# 1_P1.net
KiCad netlist of a schematic drawn in Altium Designer
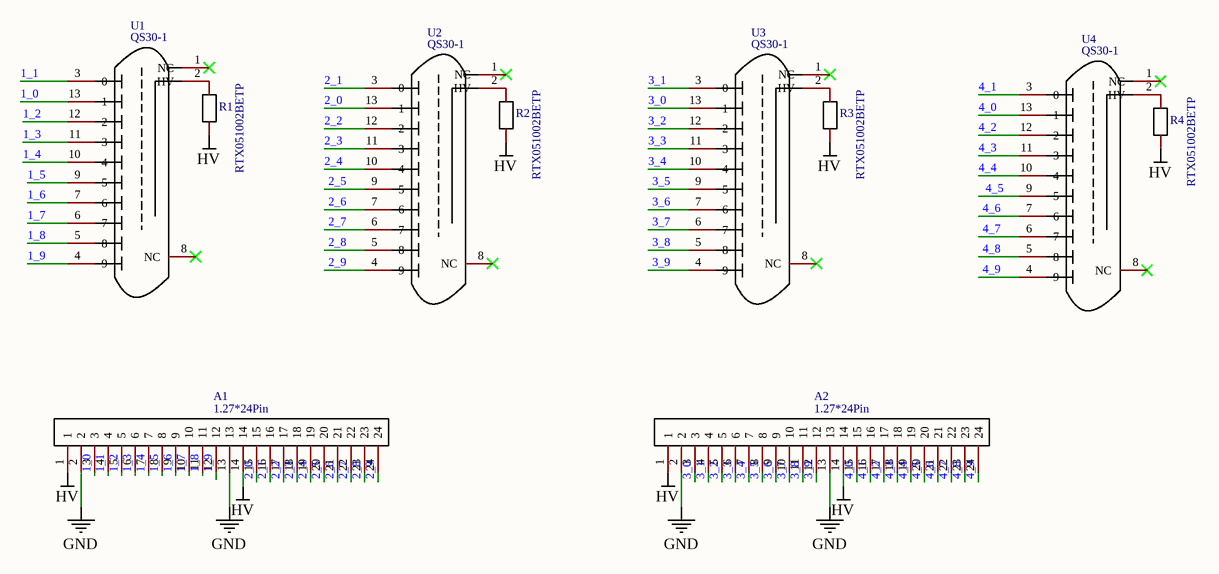
[diagram p0: 1_P1.schdoc]

(export (version "E")
  (design (tool "Eeschema 10.0.6"))
  (components
    (comp (ref "A1")
      (value "1.27*24Pin")
      (fields (field (name "NAME") "1.27*24Pin"))
      (libsource (lib "altium-import") (part "root_1_1.27*24Pin_"))
    )
    (comp (ref "A2")
      (value "1.27*24Pin")
      (fields (field (name "NAME") "1.27*24Pin"))
      (libsource (lib "altium-import") (part "root_1_1.27*24Pin_"))
    )
    (comp (ref "R1")
      (value "RTX051002BETP")
      (fields (field (name "NAME") "RTX051002BETP") (field (name "MANUFACTURER") "RALEC(旺诠)"))
      (libsource (lib "altium-import") (part "root_1_RTX051002BETP_"))
    )
    (comp (ref "R2")
      (value "RTX051002BETP")
      (fields (field (name "NAME") "RTX051002BETP") (field (name "MANUFACTURER") "RALEC(旺诠)"))
      (libsource (lib "altium-import") (part "root_1_RTX051002BETP_"))
    )
    (comp (ref "R3")
      (value "RTX051002BETP")
      (fields (field (name "NAME") "RTX051002BETP") (field (name "MANUFACTURER") "RALEC(旺诠)"))
      (libsource (lib "altium-import") (part "root_1_RTX051002BETP_"))
    )
    (comp (ref "R4")
      (value "RTX051002BETP")
      (fields (field (name "NAME") "RTX051002BETP") (field (name "MANUFACTURER") "RALEC(旺诠)"))
      (libsource (lib "altium-import") (part "root_1_RTX051002BETP_"))
    )
    (comp (ref "U1")
      (value "QS30-1")
      (fields (field (name "NAME") "QS30-1"))
      (libsource (lib "altium-import") (part "root_3_QS30-1_"))
    )
    (comp (ref "U2")
      (value "QS30-1")
      (fields (field (name "NAME") "QS30-1"))
      (libsource (lib "altium-import") (part "root_3_QS30-1_"))
    )
    (comp (ref "U3")
      (value "QS30-1")
      (fields (field (name "NAME") "QS30-1"))
      (libsource (lib "altium-import") (part "root_3_QS30-1_"))
    )
    (comp (ref "U4")
      (value "QS30-1")
      (fields (field (name "NAME") "QS30-1"))
      (libsource (lib "altium-import") (part "root_3_QS30-1_"))
    )
  )
  (nets
    (net (code "1") (name "/1_0") (class "Default")
      (node (ref "A1") (pin "3") (pinfunction "3_3") (pintype "passive"))
      (node (ref "U1") (pin "13") (pinfunction "1_13") (pintype "passive"))
    )
    (net (code "2") (name "/1_1") (class "Default")
      (node (ref "A1") (pin "4") (pinfunction "4_4") (pintype "passive"))
      (node (ref "U1") (pin "3") (pinfunction "0_3") (pintype "passive"))
    )
    (net (code "3") (name "/1_2") (class "Default")
      (node (ref "A1") (pin "5") (pinfunction "5_5") (pintype "passive"))
      (node (ref "U1") (pin "12") (pinfunction "2_12") (pintype "passive"))
    )
    (net (code "4") (name "/1_3") (class "Default")
      (node (ref "A1") (pin "6") (pinfunction "6_6") (pintype "passive"))
      (node (ref "U1") (pin "11") (pinfunction "3_11") (pintype "passive"))
    )
    (net (code "5") (name "/1_4") (class "Default")
      (node (ref "A1") (pin "7") (pinfunction "7_7") (pintype "passive"))
      (node (ref "U1") (pin "10") (pinfunction "4_10") (pintype "passive"))
    )
    (net (code "6") (name "/1_5") (class "Default")
      (node (ref "A1") (pin "8") (pinfunction "8_8") (pintype "passive"))
      (node (ref "U1") (pin "9") (pinfunction "5_9") (pintype "passive"))
    )
    (net (code "7") (name "/1_6") (class "Default")
      (node (ref "A1") (pin "9") (pinfunction "9_9") (pintype "passive"))
      (node (ref "U1") (pin "7") (pinfunction "6_7") (pintype "passive"))
    )
    (net (code "8") (name "/1_7") (class "Default")
      (node (ref "A1") (pin "10") (pinfunction "10_10") (pintype "passive"))
      (node (ref "U1") (pin "6") (pinfunction "7_6") (pintype "passive"))
    )
    (net (code "9") (name "/1_8") (class "Default")
      (node (ref "A1") (pin "11") (pinfunction "11_11") (pintype "passive"))
      (node (ref "U1") (pin "5") (pinfunction "8_5") (pintype "passive"))
    )
    (net (code "10") (name "/1_9") (class "Default")
      (node (ref "A1") (pin "12") (pinfunction "12_12") (pintype "passive"))
      (node (ref "U1") (pin "4") (pinfunction "9_4") (pintype "passive"))
    )
    (net (code "11") (name "/2_0") (class "Default")
      (node (ref "A1") (pin "15") (pinfunction "15_15") (pintype "passive"))
      (node (ref "U2") (pin "13") (pinfunction "1_13") (pintype "passive"))
    )
    (net (code "12") (name "/2_1") (class "Default")
      (node (ref "A1") (pin "16") (pinfunction "16_16") (pintype "passive"))
      (node (ref "U2") (pin "3") (pinfunction "0_3") (pintype "passive"))
    )
    (net (code "13") (name "/2_2") (class "Default")
      (node (ref "A1") (pin "17") (pinfunction "17_17") (pintype "passive"))
      (node (ref "U2") (pin "12") (pinfunction "2_12") (pintype "passive"))
    )
    (net (code "14") (name "/2_3") (class "Default")
      (node (ref "A1") (pin "18") (pinfunction "18_18") (pintype "passive"))
      (node (ref "U2") (pin "11") (pinfunction "3_11") (pintype "passive"))
    )
    (net (code "15") (name "/2_4") (class "Default")
      (node (ref "A1") (pin "19") (pinfunction "19_19") (pintype "passive"))
      (node (ref "U2") (pin "10") (pinfunction "4_10") (pintype "passive"))
    )
    (net (code "16") (name "/2_5") (class "Default")
      (node (ref "A1") (pin "20") (pinfunction "20_20") (pintype "passive"))
      (node (ref "U2") (pin "9") (pinfunction "5_9") (pintype "passive"))
    )
    (net (code "17") (name "/2_6") (class "Default")
      (node (ref "A1") (pin "21") (pinfunction "21_21") (pintype "passive"))
      (node (ref "U2") (pin "7") (pinfunction "6_7") (pintype "passive"))
    )
    (net (code "18") (name "/2_7") (class "Default")
      (node (ref "A1") (pin "22") (pinfunction "22_22") (pintype "passive"))
      (node (ref "U2") (pin "6") (pinfunction "7_6") (pintype "passive"))
    )
    (net (code "19") (name "/2_8") (class "Default")
      (node (ref "A1") (pin "23") (pinfunction "23_23") (pintype "passive"))
      (node (ref "U2") (pin "5") (pinfunction "8_5") (pintype "passive"))
    )
    (net (code "20") (name "/2_9") (class "Default")
      (node (ref "A1") (pin "24") (pinfunction "24_24") (pintype "passive"))
      (node (ref "U2") (pin "4") (pinfunction "9_4") (pintype "passive"))
    )
    (net (code "21") (name "/3_0") (class "Default")
      (node (ref "A2") (pin "3") (pinfunction "3_3") (pintype "passive"))
      (node (ref "U3") (pin "13") (pinfunction "1_13") (pintype "passive"))
    )
    (net (code "22") (name "/3_1") (class "Default")
      (node (ref "A2") (pin "4") (pinfunction "4_4") (pintype "passive"))
      (node (ref "U3") (pin "3") (pinfunction "0_3") (pintype "passive"))
    )
    (net (code "23") (name "/3_2") (class "Default")
      (node (ref "A2") (pin "5") (pinfunction "5_5") (pintype "passive"))
      (node (ref "U3") (pin "12") (pinfunction "2_12") (pintype "passive"))
    )
    (net (code "24") (name "/3_3") (class "Default")
      (node (ref "A2") (pin "6") (pinfunction "6_6") (pintype "passive"))
      (node (ref "U3") (pin "11") (pinfunction "3_11") (pintype "passive"))
    )
    (net (code "25") (name "/3_4") (class "Default")
      (node (ref "A2") (pin "7") (pinfunction "7_7") (pintype "passive"))
      (node (ref "U3") (pin "10") (pinfunction "4_10") (pintype "passive"))
    )
    (net (code "26") (name "/3_5") (class "Default")
      (node (ref "A2") (pin "8") (pinfunction "8_8") (pintype "passive"))
      (node (ref "U3") (pin "9") (pinfunction "5_9") (pintype "passive"))
    )
    (net (code "27") (name "/3_6") (class "Default")
      (node (ref "A2") (pin "9") (pinfunction "9_9") (pintype "passive"))
      (node (ref "U3") (pin "7") (pinfunction "6_7") (pintype "passive"))
    )
    (net (code "28") (name "/3_7") (class "Default")
      (node (ref "A2") (pin "10") (pinfunction "10_10") (pintype "passive"))
      (node (ref "U3") (pin "6") (pinfunction "7_6") (pintype "passive"))
    )
    (net (code "29") (name "/3_8") (class "Default")
      (node (ref "A2") (pin "11") (pinfunction "11_11") (pintype "passive"))
      (node (ref "U3") (pin "5") (pinfunction "8_5") (pintype "passive"))
    )
    (net (code "30") (name "/3_9") (class "Default")
      (node (ref "A2") (pin "12") (pinfunction "12_12") (pintype "passive"))
      (node (ref "U3") (pin "4") (pinfunction "9_4") (pintype "passive"))
    )
    (net (code "31") (name "/4_0") (class "Default")
      (node (ref "A2") (pin "15") (pinfunction "15_15") (pintype "passive"))
      (node (ref "U4") (pin "13") (pinfunction "1_13") (pintype "passive"))
    )
    (net (code "32") (name "/4_1") (class "Default")
      (node (ref "A2") (pin "16") (pinfunction "16_16") (pintype "passive"))
      (node (ref "U4") (pin "3") (pinfunction "0_3") (pintype "passive"))
    )
    (net (code "33") (name "/4_2") (class "Default")
      (node (ref "A2") (pin "17") (pinfunction "17_17") (pintype "passive"))
      (node (ref "U4") (pin "12") (pinfunction "2_12") (pintype "passive"))
    )
    (net (code "34") (name "/4_3") (class "Default")
      (node (ref "A2") (pin "18") (pinfunction "18_18") (pintype "passive"))
      (node (ref "U4") (pin "11") (pinfunction "3_11") (pintype "passive"))
    )
    (net (code "35") (name "/4_4") (class "Default")
      (node (ref "A2") (pin "19") (pinfunction "19_19") (pintype "passive"))
      (node (ref "U4") (pin "10") (pinfunction "4_10") (pintype "passive"))
    )
    (net (code "36") (name "/4_5") (class "Default")
      (node (ref "A2") (pin "20") (pinfunction "20_20") (pintype "passive"))
      (node (ref "U4") (pin "9") (pinfunction "5_9") (pintype "passive"))
    )
    (net (code "37") (name "/4_6") (class "Default")
      (node (ref "A2") (pin "21") (pinfunction "21_21") (pintype "passive"))
      (node (ref "U4") (pin "7") (pinfunction "6_7") (pintype "passive"))
    )
    (net (code "38") (name "/4_7") (class "Default")
      (node (ref "A2") (pin "22") (pinfunction "22_22") (pintype "passive"))
      (node (ref "U4") (pin "6") (pinfunction "7_6") (pintype "passive"))
    )
    (net (code "39") (name "/4_8") (class "Default")
      (node (ref "A2") (pin "23") (pinfunction "23_23") (pintype "passive"))
      (node (ref "U4") (pin "5") (pinfunction "8_5") (pintype "passive"))
    )
    (net (code "40") (name "/4_9") (class "Default")
      (node (ref "A2") (pin "24") (pinfunction "24_24") (pintype "passive"))
      (node (ref "U4") (pin "4") (pinfunction "9_4") (pintype "passive"))
    )
    (net (code "41") (name "GND") (class "Default")
      (node (ref "A1") (pin "13") (pinfunction "13_13") (pintype "passive"))
      (node (ref "A1") (pin "2") (pinfunction "2_2") (pintype "passive"))
      (node (ref "A2") (pin "13") (pinfunction "13_13") (pintype "passive"))
      (node (ref "A2") (pin "2") (pinfunction "2_2") (pintype "passive"))
    )
    (net (code "42") (name "HV") (class "Default")
      (node (ref "A1") (pin "1") (pinfunction "1_1") (pintype "passive"))
      (node (ref "A1") (pin "14") (pinfunction "14_14") (pintype "passive"))
      (node (ref "A2") (pin "1") (pinfunction "1_1") (pintype "passive"))
      (node (ref "A2") (pin "14") (pinfunction "14_14") (pintype "passive"))
      (node (ref "R1") (pin "1") (pinfunction "1_1") (pintype "passive"))
      (node (ref "R2") (pin "1") (pinfunction "1_1") (pintype "passive"))
      (node (ref "R3") (pin "1") (pinfunction "1_1") (pintype "passive"))
      (node (ref "R4") (pin "1") (pinfunction "1_1") (pintype "passive"))
    )
    (net (code "43") (name "Net-(U1-HV)") (class "Default")
      (node (ref "R1") (pin "2") (pinfunction "2_2") (pintype "passive"))
      (node (ref "U1") (pin "2") (pinfunction "HV_2") (pintype "passive"))
    )
    (net (code "44") (name "Net-(U2-HV)") (class "Default")
      (node (ref "R2") (pin "2") (pinfunction "2_2") (pintype "passive"))
      (node (ref "U2") (pin "2") (pinfunction "HV_2") (pintype "passive"))
    )
    (net (code "45") (name "Net-(U3-HV)") (class "Default")
      (node (ref "R3") (pin "2") (pinfunction "2_2") (pintype "passive"))
      (node (ref "U3") (pin "2") (pinfunction "HV_2") (pintype "passive"))
    )
    (net (code "46") (name "Net-(U4-HV)") (class "Default")
      (node (ref "R4") (pin "2") (pinfunction "2_2") (pintype "passive"))
      (node (ref "U4") (pin "2") (pinfunction "HV_2") (pintype "passive"))
    )
    (net (code "47") (name "unconnected-(U1-NC-Pad1)") (class "Default")
      (node (ref "U1") (pin "1") (pinfunction "NC_1") (pintype "passive+no_connect"))
    )
    (net (code "48") (name "unconnected-(U1-NC-Pad8)") (class "Default")
      (node (ref "U1") (pin "8") (pinfunction "NC_8") (pintype "passive+no_connect"))
    )
    (net (code "49") (name "unconnected-(U2-NC-Pad1)") (class "Default")
      (node (ref "U2") (pin "1") (pinfunction "NC_1") (pintype "passive+no_connect"))
    )
    (net (code "50") (name "unconnected-(U2-NC-Pad8)") (class "Default")
      (node (ref "U2") (pin "8") (pinfunction "NC_8") (pintype "passive+no_connect"))
    )
    (net (code "51") (name "unconnected-(U3-NC-Pad1)") (class "Default")
      (node (ref "U3") (pin "1") (pinfunction "NC_1") (pintype "passive+no_connect"))
    )
    (net (code "52") (name "unconnected-(U3-NC-Pad8)") (class "Default")
      (node (ref "U3") (pin "8") (pinfunction "NC_8") (pintype "passive+no_connect"))
    )
    (net (code "53") (name "unconnected-(U4-NC-Pad1)") (class "Default")
      (node (ref "U4") (pin "1") (pinfunction "NC_1") (pintype "passive+no_connect"))
    )
    (net (code "54") (name "unconnected-(U4-NC-Pad8)") (class "Default")
      (node (ref "U4") (pin "8") (pinfunction "NC_8") (pintype "passive+no_connect"))
    )
  )
)
